# Trap_PCB_SMT2024_N_N.net
KiCad netlist of a schematic drawn in Altium Designer
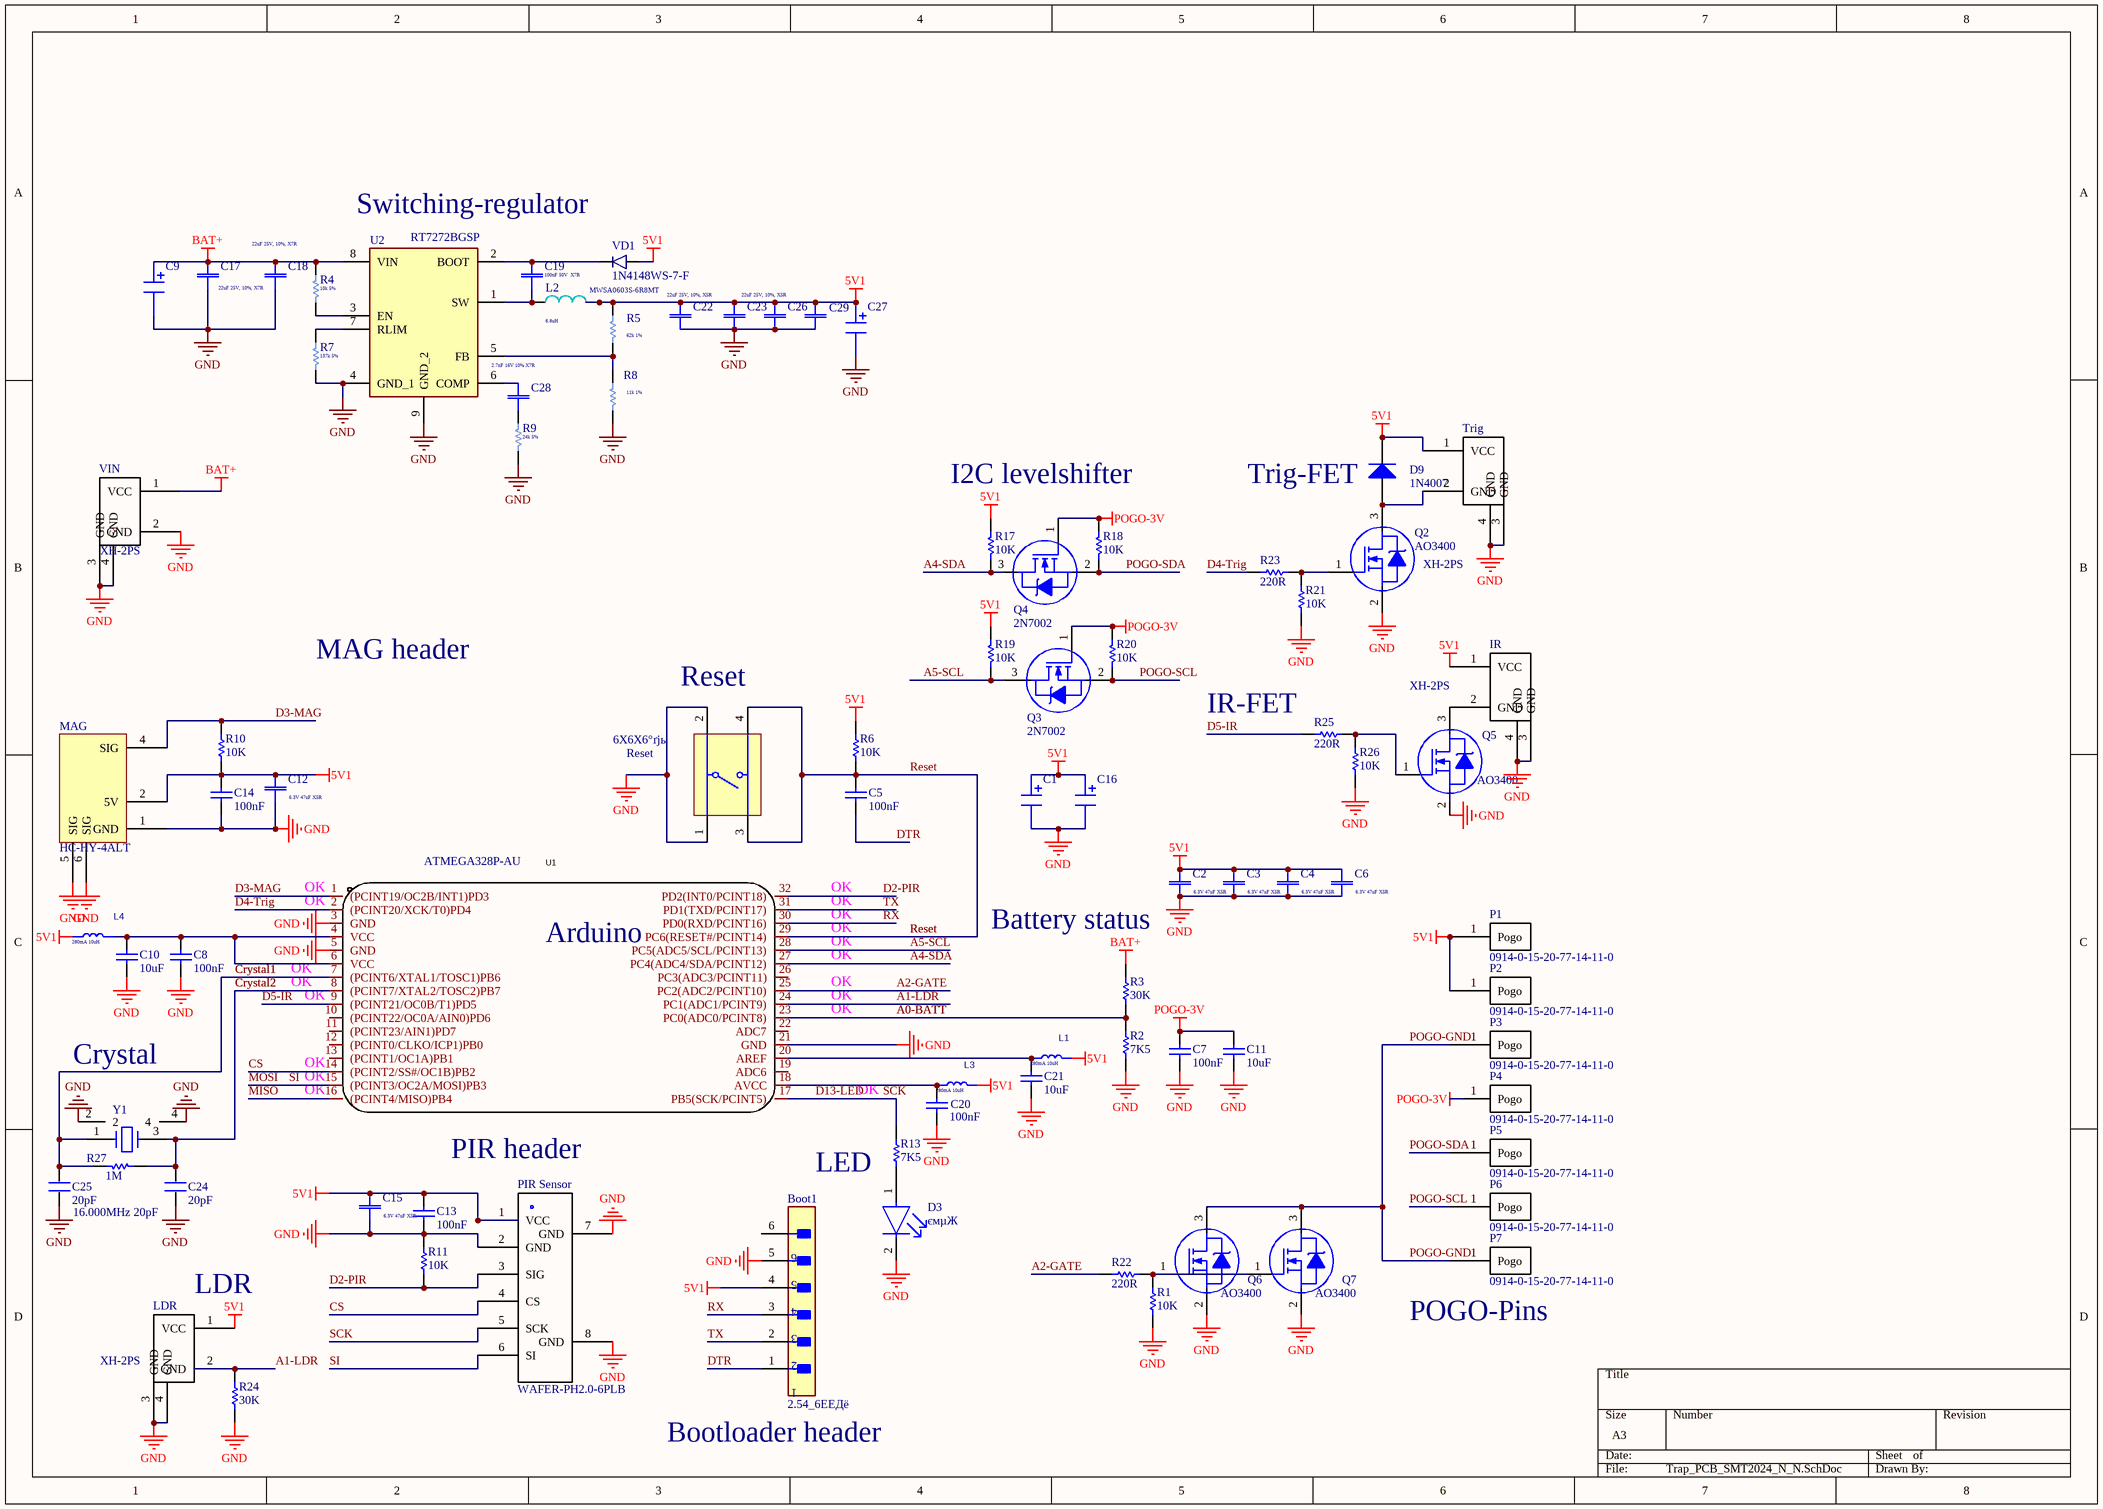
[diagram p0: Trap_PCB_SMT2024_N_N.SchDoc]

(export (version "E")
  (design (tool "Eeschema 10.0.6"))
  (components
    (comp (ref "Boot1")
      (value "2.54_6ЕЕДё")
      (footprint "FP-SWR25X-NRTC-S06-ST-BA-MFG")
      (description "CONN HEADER VERT 6POS 2.54MM")
      (fields
        (field (name "OCTOPART") "https://octopart.com/swr25x-nrtc-s06-st-ba-sullins-20912730")
        (field (name "MANUFACTURER") "Sullins")
      )
      (libsource (lib "*") (part "f2cb566baf1c37ab5a3b8e90bbeafd6"))
    )
    (comp (ref "C1")
      (value "NJCON 1026R30812R00")
      (footprint "Cap 8mm")
      (libsource (lib "MyLib1") (part "CAP 8mm"))
    )
    (comp (ref "C2")
      (value "6.3V 47uF X5R")
      (footprint "C0805(2013)")
      (description "SMD-0805")
      (libsource (lib "MyLib1") (part "C-0805"))
    )
    (comp (ref "C3")
      (value "6.3V 47uF X5R")
      (footprint "C0805(2013)")
      (description "SMD-0805")
      (libsource (lib "MyLib1") (part "C-0805"))
    )
    (comp (ref "C4")
      (value "6.3V 47uF X5R")
      (footprint "C0805(2013)")
      (description "SMD-0805")
      (libsource (lib "MyLib1") (part "C-0805"))
    )
    (comp (ref "C5")
      (value "100nF")
      (footprint "0603C")
      (description "Capacitor, Ceramic, 22 pF, +/-10 %, 100 V, -55 to 125 degC, 2-Pin THD, RoHS, Bulk")
      (libsource (lib "*") (part "CAP-NP-2"))
    )
    (comp (ref "C6")
      (value "6.3V 47uF X5R")
      (footprint "C0805(2013)")
      (description "SMD-0805")
      (libsource (lib "MyLib1") (part "C-0805"))
    )
    (comp (ref "C7")
      (value "100nF")
      (footprint "0603C")
      (description "Capacitor, Ceramic, 22 pF, +/-10 %, 100 V, -55 to 125 degC, 2-Pin THD, RoHS, Bulk")
      (libsource (lib "*") (part "CAP-NP-2"))
    )
    (comp (ref "C8")
      (value "100nF")
      (footprint "0603C")
      (description "Capacitor, Ceramic, 22 pF, +/-10 %, 100 V, -55 to 125 degC, 2-Pin THD, RoHS, Bulk")
      (libsource (lib "*") (part "CAP-NP-2"))
    )
    (comp (ref "C9")
      (value "Honor Elec HS1C567M0811PC")
      (footprint "Cap 8mm")
      (libsource (lib "MyLib1") (part "CAP 8mm"))
    )
    (comp (ref "C10")
      (value "10uF")
      (footprint "0603C")
      (description "Capacitor, Ceramic, 22 pF, +/-10 %, 100 V, -55 to 125 degC, 2-Pin THD, RoHS, Bulk")
      (libsource (lib "*") (part "CAP-NP-2"))
    )
    (comp (ref "C11")
      (value "10uF")
      (footprint "0603C")
      (description "Capacitor, Ceramic, 22 pF, +/-10 %, 100 V, -55 to 125 degC, 2-Pin THD, RoHS, Bulk")
      (libsource (lib "*") (part "CAP-NP-2"))
    )
    (comp (ref "C12")
      (value "6.3V 47uF X5R")
      (footprint "C0805(2013)")
      (description "SMD-0805")
      (libsource (lib "MyLib1") (part "C-0805"))
    )
    (comp (ref "C13")
      (value "100nF")
      (footprint "0603C")
      (description "Capacitor, Ceramic, 22 pF, +/-10 %, 100 V, -55 to 125 degC, 2-Pin THD, RoHS, Bulk")
      (libsource (lib "*") (part "CAP-NP-2"))
    )
    (comp (ref "C14")
      (value "100nF")
      (footprint "0603C")
      (description "Capacitor, Ceramic, 22 pF, +/-10 %, 100 V, -55 to 125 degC, 2-Pin THD, RoHS, Bulk")
      (libsource (lib "*") (part "CAP-NP-2"))
    )
    (comp (ref "C15")
      (value "6.3V 47uF X5R")
      (footprint "C0805(2013)")
      (description "SMD-0805")
      (libsource (lib "MyLib1") (part "C-0805"))
    )
    (comp (ref "C16")
      (value "NJCON 1026R30812R00")
      (footprint "Cap 8mm")
      (libsource (lib "MyLib1") (part "CAP 8mm"))
    )
    (comp (ref "C17")
      (value "22uF 25V, 10%, X7R")
      (footprint "C1206(3216)")
      (description "SMD-1206")
      (libsource (lib "MyLib1") (part "C-1206"))
    )
    (comp (ref "C18")
      (value "22uF 25V, 10%, X7R")
      (footprint "C1206(3216)")
      (description "SMD-1206")
      (libsource (lib "MyLib1") (part "C-1206"))
    )
    (comp (ref "C19")
      (value "100nF 50V  X7R")
      (footprint "C0603(1608)")
      (description "SMD-0603")
      (libsource (lib "MyLib1") (part "C-0603"))
    )
    (comp (ref "C20")
      (value "100nF")
      (footprint "0603C")
      (description "Capacitor, Ceramic, 22 pF, +/-10 %, 100 V, -55 to 125 degC, 2-Pin THD, RoHS, Bulk")
      (libsource (lib "*") (part "CAP-NP-2"))
    )
    (comp (ref "C21")
      (value "10uF")
      (footprint "0603C")
      (description "Capacitor, Ceramic, 22 pF, +/-10 %, 100 V, -55 to 125 degC, 2-Pin THD, RoHS, Bulk")
      (libsource (lib "*") (part "CAP-NP-2"))
    )
    (comp (ref "C22")
      (value "22uF 25V, 10%, X5R")
      (footprint "C0805(2013)")
      (description "SMD-0805")
      (libsource (lib "MyLib1") (part "C-0805"))
    )
    (comp (ref "C23")
      (value "22uF 25V, 10%, X5R")
      (footprint "C0805(2013)")
      (description "SMD-0805")
      (libsource (lib "MyLib1") (part "C-0805"))
    )
    (comp (ref "C24") (value "20pF") (footprint "0603C") (libsource (lib "*") (part "C")))
    (comp (ref "C25") (value "20pF") (footprint "0603C") (libsource (lib "*") (part "C")))
    (comp (ref "C26")
      (value "22uF 25V, 10%, X5R")
      (footprint "C0805(2013)")
      (description "SMD-0805")
      (libsource (lib "MyLib1") (part "C-0805"))
    )
    (comp (ref "C27")
      (value "NJCON 1026R30812R00")
      (footprint "Cap 8mm")
      (libsource (lib "MyLib1") (part "CAP 8mm"))
    )
    (comp (ref "C28")
      (value "2.7nF 16V 10% X7R")
      (footprint "C0603(1608)")
      (description "SMD-0603")
      (libsource (lib "MyLib1") (part "C-0603"))
    )
    (comp (ref "C29")
      (value "22uF 25V, 10%, X5R")
      (footprint "C0805(2013)")
      (description "SMD-0805")
      (libsource (lib "MyLib1") (part "C-0805"))
    )
    (comp (ref "D3")
      (value "ємµЖ")
      (footprint "0603LED")
      (description "LED YELLOW DIFFUSED T-1 T/H")
      (fields (field (name "MANUFACTURER") "Broadcom"))
      (libsource (lib "*") (part "8706943c75ba83719d021d2fdc84c58"))
    )
    (comp (ref "D9")
      (value "1N4007")
      (footprint "SMA")
      (description "Default Diode")
      (fields (field (name "PUBLISHER") "Altium Limited"))
      (libsource (lib "*") (part "Diode"))
    )
    (comp (ref "IR") (value "XH-2PS") (footprint "CNS_2.5-2") (libsource (lib "*") (part "JST HXP2")))
    (comp (ref "L1")
      (value "280mA 10uH")
      (footprint "R0603")
      (description "FTW1608FE100KT")
      (fields (field (name "Comment") "L-0603"))
      (libsource (lib "MyLib1") (part "L-0603"))
    )
    (comp (ref "L2")
      (value "MWSA0603S-6R8MT")
      (footprint "L (7.00mm x 6.60mm)")
      (description "6.8uH 5A 48mΩ SMD (7.00mm x 6.60mm)")
      (fields (field (name "ALTIUM_VALUE") "6.8uH"))
      (libsource (lib "MyLib1") (part "MWSA0603S-6R8MT"))
    )
    (comp (ref "L3")
      (value "280mA 10uH")
      (footprint "R0603")
      (description "FTW1608FE100KT")
      (fields (field (name "Comment") "L-0603"))
      (libsource (lib "MyLib1") (part "L-0603"))
    )
    (comp (ref "L4")
      (value "280mA 10uH")
      (footprint "R0603")
      (description "FTW1608FE100KT")
      (fields (field (name "Comment") "L-0603"))
      (libsource (lib "MyLib1") (part "L-0603"))
    )
    (comp (ref "LDR") (value "XH-2PS") (footprint "CNS_2.5-2") (libsource (lib "*") (part "JST HXP2")))
    (comp (ref "MAG")
      (value "HC-HY-4ALT")
      (footprint "CNS_4P-P2.0")
      (libsource (lib "*") (part "MAG Sensor"))
    )
    (comp (ref "P1")
      (value "0914-0-15-20-77-14-11-0")
      (footprint "0914-0-15-20-77-14-11-0")
      (description "CONTACT SPRING LOADED T/H GOLD")
      (libsource (lib "*") (part "0914-0-15-20-77-14-11-0"))
    )
    (comp (ref "P2")
      (value "0914-0-15-20-77-14-11-0")
      (footprint "0914-0-15-20-77-14-11-0")
      (description "CONTACT SPRING LOADED T/H GOLD")
      (libsource (lib "*") (part "0914-0-15-20-77-14-11-0"))
    )
    (comp (ref "P3")
      (value "0914-0-15-20-77-14-11-0")
      (footprint "0914-0-15-20-77-14-11-0")
      (description "CONTACT SPRING LOADED T/H GOLD")
      (libsource (lib "*") (part "0914-0-15-20-77-14-11-0"))
    )
    (comp (ref "P4")
      (value "0914-0-15-20-77-14-11-0")
      (footprint "0914-0-15-20-77-14-11-0")
      (description "CONTACT SPRING LOADED T/H GOLD")
      (libsource (lib "*") (part "0914-0-15-20-77-14-11-0"))
    )
    (comp (ref "P5")
      (value "0914-0-15-20-77-14-11-0")
      (footprint "0914-0-15-20-77-14-11-0")
      (description "CONTACT SPRING LOADED T/H GOLD")
      (libsource (lib "*") (part "0914-0-15-20-77-14-11-0"))
    )
    (comp (ref "P6")
      (value "0914-0-15-20-77-14-11-0")
      (footprint "0914-0-15-20-77-14-11-0")
      (description "CONTACT SPRING LOADED T/H GOLD")
      (libsource (lib "*") (part "0914-0-15-20-77-14-11-0"))
    )
    (comp (ref "P7")
      (value "0914-0-15-20-77-14-11-0")
      (footprint "0914-0-15-20-77-14-11-0")
      (description "CONTACT SPRING LOADED T/H GOLD")
      (libsource (lib "*") (part "0914-0-15-20-77-14-11-0"))
    )
    (comp (ref "PIR Sensor")
      (value "WAFER-PH2.0-6PLB")
      (footprint "CNS-2.0-6")
      (libsource (lib "*") (part "JST - PH-6p - 2.0mm"))
    )
    (comp (ref "Q2") (value "AO3400") (footprint "SOT-23") (libsource (lib "") (part "IRF640N_1")))
    (comp (ref "Q3") (value "2N7002") (footprint "SOT-23") (libsource (lib "Schlib1") (part "IRF640N")))
    (comp (ref "Q4") (value "2N7002") (footprint "SOT-23") (libsource (lib "Schlib1") (part "IRF640N")))
    (comp (ref "Q5") (value "AO3400") (footprint "SOT-23") (libsource (lib "") (part "IRF640N_1")))
    (comp (ref "Q6") (value "AO3400") (footprint "SOT-23") (libsource (lib "") (part "IRF640N_1")))
    (comp (ref "Q7") (value "AO3400") (footprint "SOT-23") (libsource (lib "") (part "IRF640N_1")))
    (comp (ref "R1")
      (value "10K")
      (footprint "0603R")
      (fields (field (name "TOLERANCE") "ЎА5%"))
      (libsource (lib "*") (part "RES-2"))
    )
    (comp (ref "R2")
      (value "7K5")
      (footprint "0603R")
      (fields (field (name "TOLERANCE") "ЎА5%"))
      (libsource (lib "*") (part "RES-2"))
    )
    (comp (ref "R3")
      (value "30K")
      (footprint "0603R")
      (fields (field (name "TOLERANCE") "ЎА5%"))
      (libsource (lib "*") (part "RES-2"))
    )
    (comp (ref "R4")
      (value "10k 5%")
      (footprint "R0603")
      (description "SMD 0603 0.1W 5% 50V")
      (libsource (lib "MyLib1") (part "R-0603"))
    )
    (comp (ref "R5")
      (value "62k 1%")
      (footprint "R0603")
      (description "SMD 0603 0.1W 5% 50V")
      (libsource (lib "MyLib1") (part "R-0603"))
    )
    (comp (ref "R6")
      (value "10K")
      (footprint "0603R")
      (fields (field (name "TOLERANCE") "ЎА5%"))
      (libsource (lib "*") (part "RES-2"))
    )
    (comp (ref "R7")
      (value "137k 5%")
      (footprint "R0603")
      (description "SMD 0603 0.1W 5% 50V")
      (libsource (lib "MyLib1") (part "R-0603"))
    )
    (comp (ref "R8")
      (value "11k 1%")
      (footprint "R0603")
      (description "SMD 0603 0.1W 5% 50V")
      (libsource (lib "MyLib1") (part "R-0603"))
    )
    (comp (ref "R9")
      (value "24k 5%")
      (footprint "R0603")
      (description "SMD 0603 0.1W 5% 50V")
      (libsource (lib "MyLib1") (part "R-0603"))
    )
    (comp (ref "R10")
      (value "10K")
      (footprint "0603R")
      (fields (field (name "TOLERANCE") "ЎА5%"))
      (libsource (lib "*") (part "RES-2"))
    )
    (comp (ref "R11")
      (value "10K")
      (footprint "0603R")
      (fields (field (name "TOLERANCE") "ЎА5%"))
      (libsource (lib "*") (part "RES-2"))
    )
    (comp (ref "R13")
      (value "7K5")
      (footprint "0603R")
      (fields (field (name "TOLERANCE") "ЎА5%"))
      (libsource (lib "*") (part "RES-2"))
    )
    (comp (ref "R17")
      (value "10K")
      (footprint "0603R")
      (fields (field (name "TOLERANCE") "ЎА5%"))
      (libsource (lib "*") (part "RES-2"))
    )
    (comp (ref "R18")
      (value "10K")
      (footprint "0603R")
      (fields (field (name "TOLERANCE") "ЎА5%"))
      (libsource (lib "*") (part "RES-2"))
    )
    (comp (ref "R19")
      (value "10K")
      (footprint "0603R")
      (fields (field (name "TOLERANCE") "ЎА5%"))
      (libsource (lib "*") (part "RES-2"))
    )
    (comp (ref "R20")
      (value "10K")
      (footprint "0603R")
      (fields (field (name "TOLERANCE") "ЎА5%"))
      (libsource (lib "*") (part "RES-2"))
    )
    (comp (ref "R21")
      (value "10K")
      (footprint "0603R")
      (fields (field (name "TOLERANCE") "ЎА5%"))
      (libsource (lib "*") (part "RES-2"))
    )
    (comp (ref "R22")
      (value "220R")
      (footprint "0603R")
      (fields (field (name "TOLERANCE") "ЎА5%"))
      (libsource (lib "*") (part "RES-2"))
    )
    (comp (ref "R23")
      (value "220R")
      (footprint "0603R")
      (fields (field (name "TOLERANCE") "ЎА5%"))
      (libsource (lib "*") (part "RES-2"))
    )
    (comp (ref "R24")
      (value "30K")
      (footprint "0603R")
      (fields (field (name "TOLERANCE") "ЎА5%"))
      (libsource (lib "*") (part "RES-2"))
    )
    (comp (ref "R25")
      (value "220R")
      (footprint "0603R")
      (fields (field (name "TOLERANCE") "ЎА5%"))
      (libsource (lib "*") (part "RES-2"))
    )
    (comp (ref "R26")
      (value "10K")
      (footprint "0603R")
      (fields (field (name "TOLERANCE") "ЎА5%"))
      (libsource (lib "*") (part "RES-2"))
    )
    (comp (ref "R27")
      (value "1M")
      (footprint "0603R")
      (description "Resistor")
      (fields (field (name "PUBLISHER") "Altium Limited"))
      (libsource (lib "Miscellaneous Devices") (part "Res1"))
    )
    (comp (ref "Reset")
      (value "6X6X6°ґјь")
      (footprint "SW-4P-6X6")
      (description "Tactile Switch, SPST-NO, 0.05 A, 5 to 24 V, -25 to 70 degC, 4-Pin THD, RoHS, Bulk")
      (libsource (lib "*") (part "SW-SPST-4_A"))
    )
    (comp (ref "Trig") (value "XH-2PS") (footprint "CNS_2.5-2") (libsource (lib "*") (part "JST HXP2")))
    (comp (ref "U1")
      (value "ATMEGA328P-AU")
      (footprint "TQFP-32_L7.0-W7.0-P0.80-LS9.0-BL")
      (libsource (lib "altium-import") (part "root_0_ATMEGA328P-AU_"))
    )
    (comp (ref "U2")
      (value "RT7272BGSP")
      (footprint "SOIC8 +")
      (fields (field (name "MF") "Richtek USA"))
      (libsource (lib "MYLIB1") (part "RT7272BGSP"))
    )
    (comp (ref "VD1")
      (value "1N4148WS-7-F")
      (footprint "SOD-323")
      (libsource (lib "MYLIB1") (part "1N4148WS-7-F"))
    )
    (comp (ref "VIN") (value "XH-2PS") (footprint "CNS_2.5-2") (libsource (lib "*") (part "JST HXP2")))
    (comp (ref "Y1")
      (value "16.000MHz 20pF")
      (footprint "X3225")
      (description "R25010031/№¤ТµC/Пы·СA/ѕ§МеХсµґЖч/8.000M/20pF/ЎА30ppm/49USM/ROHS/-10Ўж~+70Ўж")
      (libsource (lib "R25_IC") (part "R25010031"))
    )
  )
  (nets
    (net (code "1") (name "/A0-BATT") (class "Default")
      (node (ref "R2") (pin "1") (pinfunction "1_1") (pintype "passive"))
      (node (ref "R3") (pin "2") (pinfunction "2_2") (pintype "passive"))
      (node (ref "U1") (pin "23") (pinfunction "PC0(ADC0/PCINT8)_23") (pintype "passive"))
    )
    (net (code "2") (name "/A1-LDR") (class "Default")
      (node (ref "LDR") (pin "2") (pinfunction "GND_2") (pintype "passive"))
      (node (ref "R24") (pin "2") (pinfunction "2_2") (pintype "passive"))
      (node (ref "U1") (pin "24") (pinfunction "PC1(ADC1/PCINT9)_24") (pintype "passive"))
    )
    (net (code "3") (name "/A2-GATE") (class "Default")
      (node (ref "R22") (pin "2") (pinfunction "2_2") (pintype "passive"))
      (node (ref "U1") (pin "25") (pinfunction "PC2(ADC2/PCINT10)_25") (pintype "passive"))
    )
    (net (code "4") (name "/A4-SDA") (class "Default")
      (node (ref "Q4") (pin "3") (pinfunction "3_3") (pintype "passive"))
      (node (ref "R17") (pin "1") (pinfunction "1_1") (pintype "passive"))
      (node (ref "U1") (pin "27") (pinfunction "PC4(ADC4/SDA/PCINT12)_27") (pintype "passive"))
    )
    (net (code "5") (name "/A5-SCL") (class "Default")
      (node (ref "Q3") (pin "3") (pinfunction "3_3") (pintype "passive"))
      (node (ref "R19") (pin "1") (pinfunction "1_1") (pintype "passive"))
      (node (ref "U1") (pin "28") (pinfunction "PC5(ADC5/SCL/PCINT13)_28") (pintype "passive"))
    )
    (net (code "6") (name "/CS") (class "Default")
      (node (ref "PIR Sensor") (pin "4") (pinfunction "CS_4") (pintype "passive"))
      (node (ref "U1") (pin "14") (pinfunction "(PCINT2/SS#/OC1B)PB2_14") (pintype "passive"))
    )
    (net (code "7") (name "/Crystal1") (class "Default")
      (node (ref "C25") (pin "2") (pintype "passive"))
      (node (ref "R27") (pin "2") (pinfunction "2_2") (pintype "passive"))
      (node (ref "U1") (pin "7") (pinfunction "(PCINT6/XTAL1/TOSC1)PB6_7") (pintype "passive"))
      (node (ref "Y1") (pin "1") (pinfunction "1_1") (pintype "passive"))
    )
    (net (code "8") (name "/Crystal2") (class "Default")
      (node (ref "C24") (pin "2") (pintype "passive"))
      (node (ref "R27") (pin "1") (pinfunction "1_1") (pintype "passive"))
      (node (ref "U1") (pin "8") (pinfunction "(PCINT7/XTAL2/TOSC2)PB7_8") (pintype "passive"))
      (node (ref "Y1") (pin "3") (pinfunction "3_3") (pintype "passive"))
    )
    (net (code "9") (name "/D2-PIR") (class "Default")
      (node (ref "PIR Sensor") (pin "3") (pinfunction "SIG_3") (pintype "passive"))
      (node (ref "R11") (pin "2") (pinfunction "2_2") (pintype "passive"))
      (node (ref "U1") (pin "32") (pinfunction "PD2(INT0/PCINT18)_32") (pintype "passive"))
    )
    (net (code "10") (name "/D3-MAG") (class "Default")
      (node (ref "MAG") (pin "4") (pinfunction "SIG_4") (pintype "passive"))
      (node (ref "R10") (pin "1") (pinfunction "1_1") (pintype "passive"))
      (node (ref "U1") (pin "1") (pinfunction "(PCINT19/OC2B/INT1)PD3_1") (pintype "passive"))
    )
    (net (code "11") (name "/D4-Trig") (class "Default")
      (node (ref "R23") (pin "2") (pinfunction "2_2") (pintype "passive"))
      (node (ref "U1") (pin "2") (pinfunction "(PCINT20/XCK/T0)PD4_2") (pintype "passive"))
    )
    (net (code "12") (name "/D5-IR") (class "Default")
      (node (ref "R25") (pin "2") (pinfunction "2_2") (pintype "passive"))
      (node (ref "U1") (pin "9") (pinfunction "(PCINT21/OC0B/T1)PD5_9") (pintype "passive"))
    )
    (net (code "13") (name "/D13-LED") (class "Default")
      (node (ref "PIR Sensor") (pin "5") (pinfunction "SCK_5") (pintype "passive"))
      (node (ref "R13") (pin "2") (pinfunction "2_2") (pintype "passive"))
      (node (ref "U1") (pin "17") (pinfunction "PB5(SCK/PCINT5)_17") (pintype "passive"))
    )
    (net (code "14") (name "/DTR") (class "Default")
      (node (ref "Boot1") (pin "1") (pinfunction "1_1") (pintype "passive"))
      (node (ref "C5") (pin "1") (pinfunction "1_1") (pintype "passive"))
    )
    (net (code "15") (name "/MISO") (class "Default")
      (node (ref "U1") (pin "16") (pinfunction "(PCINT4/MISO)PB4_16") (pintype "passive"))
    )
    (net (code "16") (name "/MOSI") (class "Default")
      (node (ref "PIR Sensor") (pin "6") (pinfunction "SI_6") (pintype "passive"))
      (node (ref "U1") (pin "15") (pinfunction "(PCINT3/OC2A/MOSI)PB3_15") (pintype "passive"))
    )
    (net (code "17") (name "/POGO-GND") (class "Default")
      (node (ref "P3") (pin "1") (pinfunction "Pogo_1") (pintype "passive"))
      (node (ref "P7") (pin "1") (pinfunction "Pogo_1") (pintype "passive"))
      (node (ref "Q6") (pin "3") (pinfunction "3_3") (pintype "passive"))
      (node (ref "Q7") (pin "3") (pinfunction "3_3") (pintype "passive"))
    )
    (net (code "18") (name "/POGO-SCL") (class "Default")
      (node (ref "P6") (pin "1") (pinfunction "Pogo_1") (pintype "passive"))
      (node (ref "Q3") (pin "2") (pinfunction "2_2") (pintype "passive"))
      (node (ref "R20") (pin "1") (pinfunction "1_1") (pintype "passive"))
    )
    (net (code "19") (name "/POGO-SDA") (class "Default")
      (node (ref "P5") (pin "1") (pinfunction "Pogo_1") (pintype "passive"))
      (node (ref "Q4") (pin "2") (pinfunction "2_2") (pintype "passive"))
      (node (ref "R18") (pin "1") (pinfunction "1_1") (pintype "passive"))
    )
    (net (code "20") (name "/RX") (class "Default")
      (node (ref "Boot1") (pin "3") (pinfunction "3_3") (pintype "passive"))
      (node (ref "U1") (pin "30") (pinfunction "PD0(RXD/PCINT16)_30") (pintype "passive"))
    )
    (net (code "21") (name "/Reset") (class "Default")
      (node (ref "C5") (pin "2") (pinfunction "2_2") (pintype "passive"))
      (node (ref "R6") (pin "2") (pinfunction "2_2") (pintype "passive"))
      (node (ref "Reset") (pin "3") (pinfunction "3_3") (pintype "passive"))
      (node (ref "Reset") (pin "4") (pinfunction "4_4") (pintype "passive"))
      (node (ref "U1") (pin "29") (pinfunction "PC6(RESET#/PCINT14)_29") (pintype "passive"))
    )
    (net (code "22") (name "/TX") (class "Default")
      (node (ref "Boot1") (pin "2") (pinfunction "2_2") (pintype "passive"))
      (node (ref "U1") (pin "31") (pinfunction "PD1(TXD/PCINT17)_31") (pintype "passive"))
    )
    (net (code "23") (name "5V1") (class "Default")
      (node (ref "Boot1") (pin "4") (pinfunction "4_4") (pintype "passive"))
      (node (ref "C1") (pin "1") (pintype "passive"))
      (node (ref "C12") (pin "2") (pinfunction "2_2") (pintype "passive"))
      (node (ref "C13") (pin "2") (pinfunction "2_2") (pintype "passive"))
      (node (ref "C14") (pin "2") (pinfunction "2_2") (pintype "passive"))
      (node (ref "C15") (pin "2") (pinfunction "2_2") (pintype "passive"))
      (node (ref "C16") (pin "1") (pintype "passive"))
      (node (ref "C2") (pin "2") (pinfunction "2_2") (pintype "passive"))
      (node (ref "C22") (pin "2") (pinfunction "2_2") (pintype "passive"))
      (node (ref "C23") (pin "2") (pinfunction "2_2") (pintype "passive"))
      (node (ref "C26") (pin "2") (pinfunction "2_2") (pintype "passive"))
      (node (ref "C27") (pin "1") (pintype "passive"))
      (node (ref "C29") (pin "2") (pinfunction "2_2") (pintype "passive"))
      (node (ref "C3") (pin "2") (pinfunction "2_2") (pintype "passive"))
      (node (ref "C4") (pin "2") (pinfunction "2_2") (pintype "passive"))
      (node (ref "C6") (pin "2") (pinfunction "2_2") (pintype "passive"))
      (node (ref "D9") (pin "2") (pinfunction "K_2") (pintype "passive"))
      (node (ref "IR") (pin "1") (pinfunction "VCC_1") (pintype "passive"))
      (node (ref "L1") (pin "2") (pinfunction "2_2") (pintype "passive"))
      (node (ref "L2") (pin "2") (pintype "passive"))
      (node (ref "L3") (pin "2") (pinfunction "2_2") (pintype "passive"))
      (node (ref "L4") (pin "1") (pinfunction "1_1") (pintype "passive"))
      (node (ref "LDR") (pin "1") (pinfunction "VCC_1") (pintype "passive"))
      (node (ref "MAG") (pin "2") (pinfunction "5V_2") (pintype "passive"))
      (node (ref "P1") (pin "1") (pinfunction "Pogo_1") (pintype "passive"))
      (node (ref "P2") (pin "1") (pinfunction "Pogo_1") (pintype "passive"))
      (node (ref "PIR Sensor") (pin "1") (pinfunction "VCC_1") (pintype "passive"))
      (node (ref "R10") (pin "2") (pinfunction "2_2") (pintype "passive"))
      (node (ref "R17") (pin "2") (pinfunction "2_2") (pintype "passive"))
      (node (ref "R19") (pin "2") (pinfunction "2_2") (pintype "passive"))
      (node (ref "R5") (pin "1") (pinfunction "1_1") (pintype "passive"))
      (node (ref "R6") (pin "1") (pinfunction "1_1") (pintype "passive"))
      (node (ref "Trig") (pin "1") (pinfunction "VCC_1") (pintype "passive"))
      (node (ref "VD1") (pin "2") (pinfunction "A_2") (pintype "passive"))
    )
    (net (code "24") (name "BAT+") (class "Default")
      (node (ref "C17") (pin "2") (pinfunction "2_2") (pintype "passive"))
      (node (ref "C18") (pin "2") (pinfunction "2_2") (pintype "passive"))
      (node (ref "C9") (pin "1") (pintype "passive"))
      (node (ref "R3") (pin "1") (pinfunction "1_1") (pintype "passive"))
      (node (ref "R4") (pin "1") (pinfunction "1_1") (pintype "passive"))
      (node (ref "U2") (pin "8") (pinfunction "VIN_8") (pintype "passive"))
      (node (ref "VIN") (pin "1") (pinfunction "VCC_1") (pintype "passive"))
    )
    (net (code "25") (name "GND") (class "Default")
      (node (ref "Boot1") (pin "5") (pinfunction "5_5") (pintype "passive"))
      (node (ref "C1") (pin "2") (pintype "passive"))
      (node (ref "C10") (pin "1") (pinfunction "1_1") (pintype "passive"))
      (node (ref "C11") (pin "1") (pinfunction "1_1") (pintype "passive"))
      (node (ref "C12") (pin "1") (pinfunction "1_1") (pintype "passive"))
      (node (ref "C13") (pin "1") (pinfunction "1_1") (pintype "passive"))
      (node (ref "C14") (pin "1") (pinfunction "1_1") (pintype "passive"))
      (node (ref "C15") (pin "1") (pinfunction "1_1") (pintype "passive"))
      (node (ref "C16") (pin "2") (pintype "passive"))
      (node (ref "C17") (pin "1") (pinfunction "1_1") (pintype "passive"))
      (node (ref "C18") (pin "1") (pinfunction "1_1") (pintype "passive"))
      (node (ref "C2") (pin "1") (pinfunction "1_1") (pintype "passive"))
      (node (ref "C20") (pin "1") (pinfunction "1_1") (pintype "passive"))
      (node (ref "C21") (pin "1") (pinfunction "1_1") (pintype "passive"))
      (node (ref "C22") (pin "1") (pinfunction "1_1") (pintype "passive"))
      (node (ref "C23") (pin "1") (pinfunction "1_1") (pintype "passive"))
      (node (ref "C24") (pin "1") (pintype "passive"))
      (node (ref "C25") (pin "1") (pintype "passive"))
      (node (ref "C26") (pin "1") (pinfunction "1_1") (pintype "passive"))
      (node (ref "C27") (pin "2") (pintype "passive"))
      (node (ref "C29") (pin "1") (pinfunction "1_1") (pintype "passive"))
      (node (ref "C3") (pin "1") (pinfunction "1_1") (pintype "passive"))
      (node (ref "C4") (pin "1") (pinfunction "1_1") (pintype "passive"))
      (node (ref "C6") (pin "1") (pinfunction "1_1") (pintype "passive"))
      (node (ref "C7") (pin "1") (pinfunction "1_1") (pintype "passive"))
      (node (ref "C8") (pin "1") (pinfunction "1_1") (pintype "passive"))
      (node (ref "C9") (pin "2") (pintype "passive"))
      (node (ref "D3") (pin "2") (pinfunction "A_2") (pintype "passive"))
      (node (ref "IR") (pin "3") (pinfunction "GND_3") (pintype "passive"))
      (node (ref "IR") (pin "4") (pinfunction "GND_4") (pintype "passive"))
      (node (ref "LDR") (pin "3") (pinfunction "GND_3") (pintype "passive"))
      (node (ref "LDR") (pin "4") (pinfunction "GND_4") (pintype "passive"))
      (node (ref "MAG") (pin "1") (pinfunction "GND_1") (pintype "passive"))
      (node (ref "MAG") (pin "5") (pinfunction "SIG_5") (pintype "passive"))
      (node (ref "MAG") (pin "6") (pinfunction "SIG_6") (pintype "passive"))
      (node (ref "PIR Sensor") (pin "2") (pinfunction "GND_2") (pintype "passive"))
      (node (ref "PIR Sensor") (pin "7") (pinfunction "GND_7") (pintype "passive"))
      (node (ref "PIR Sensor") (pin "8") (pinfunction "GND_8") (pintype "passive"))
      (node (ref "Q2") (pin "2") (pinfunction "2_2") (pintype "passive"))
      (node (ref "Q5") (pin "2") (pinfunction "2_2") (pintype "passive"))
      (node (ref "Q6") (pin "2") (pinfunction "2_2") (pintype "passive"))
      (node (ref "Q7") (pin "2") (pinfunction "2_2") (pintype "passive"))
      (node (ref "R1") (pin "1") (pinfunction "1_1") (pintype "passive"))
      (node (ref "R11") (pin "1") (pinfunction "1_1") (pintype "passive"))
      (node (ref "R2") (pin "2") (pinfunction "2_2") (pintype "passive"))
      (node (ref "R21") (pin "1") (pinfunction "1_1") (pintype "passive"))
      (node (ref "R24") (pin "1") (pinfunction "1_1") (pintype "passive"))
      (node (ref "R26") (pin "1") (pinfunction "1_1") (pintype "passive"))
      (node (ref "R7") (pin "2") (pinfunction "2_2") (pintype "passive"))
      (node (ref "R8") (pin "2") (pinfunction "2_2") (pintype "passive"))
      (node (ref "R9") (pin "2") (pinfunction "2_2") (pintype "passive"))
      (node (ref "Reset") (pin "1") (pinfunction "1_1") (pintype "passive"))
      (node (ref "Reset") (pin "2") (pinfunction "2_2") (pintype "passive"))
      (node (ref "Trig") (pin "3") (pinfunction "GND_3") (pintype "passive"))
      (node (ref "Trig") (pin "4") (pinfunction "GND_4") (pintype "passive"))
      (node (ref "U1") (pin "21") (pinfunction "GND_21") (pintype "passive"))
      (node (ref "U1") (pin "3") (pinfunction "GND_3") (pintype "passive"))
      (node (ref "U1") (pin "5") (pinfunction "GND_5") (pintype "passive"))
      (node (ref "U2") (pin "4") (pinfunction "GND_1_4") (pintype "passive"))
      (node (ref "U2") (pin "9") (pinfunction "GND_2_9") (pintype "passive"))
      (node (ref "VIN") (pin "2") (pinfunction "GND_2") (pintype "passive"))
      (node (ref "VIN") (pin "3") (pinfunction "GND_3") (pintype "passive"))
      (node (ref "VIN") (pin "4") (pinfunction "GND_4") (pintype "passive"))
      (node (ref "Y1") (pin "2") (pinfunction "2_2") (pintype "passive"))
      (node (ref "Y1") (pin "4") (pinfunction "4_4") (pintype "passive"))
    )
    (net (code "26") (name "Net-(C10-Pad2)") (class "Default")
      (node (ref "C10") (pin "2") (pinfunction "2_2") (pintype "passive"))
      (node (ref "C8") (pin "2") (pinfunction "2_2") (pintype "passive"))
      (node (ref "L4") (pin "2") (pinfunction "2_2") (pintype "passive"))
      (node (ref "U1") (pin "4") (pinfunction "VCC_4") (pintype "passive"))
      (node (ref "U1") (pin "6") (pinfunction "VCC_6") (pintype "passive"))
    )
    (net (code "27") (name "Net-(C28-Pad1)") (class "Default")
      (node (ref "C28") (pin "1") (pinfunction "1_1") (pintype "passive"))
      (node (ref "R9") (pin "1") (pinfunction "1_1") (pintype "passive"))
    )
    (net (code "28") (name "Net-(D3-C)") (class "Default")
      (node (ref "D3") (pin "1") (pinfunction "C_1") (pintype "passive"))
      (node (ref "R13") (pin "1") (pinfunction "1_1") (pintype "passive"))
    )
    (net (code "29") (name "Net-(D9-A)") (class "Default")
      (node (ref "D9") (pin "1") (pinfunction "A_1") (pintype "passive"))
      (node (ref "Q2") (pin "3") (pinfunction "3_3") (pintype "passive"))
      (node (ref "Trig") (pin "2") (pinfunction "GND_2") (pintype "passive"))
    )
    (net (code "30") (name "Net-(IR-GND-Pad2)") (class "Default")
      (node (ref "IR") (pin "2") (pinfunction "GND_2") (pintype "passive"))
      (node (ref "Q5") (pin "3") (pinfunction "3_3") (pintype "passive"))
    )
    (net (code "31") (name "Net-(Q2-Pad1)") (class "Default")
      (node (ref "Q2") (pin "1") (pinfunction "1_1") (pintype "passive"))
      (node (ref "R21") (pin "2") (pinfunction "2_2") (pintype "passive"))
      (node (ref "R23") (pin "1") (pinfunction "1_1") (pintype "passive"))
    )
    (net (code "32") (name "Net-(Q5-Pad1)") (class "Default")
      (node (ref "Q5") (pin "1") (pinfunction "1_1") (pintype "passive"))
      (node (ref "R25") (pin "1") (pinfunction "1_1") (pintype "passive"))
      (node (ref "R26") (pin "2") (pinfunction "2_2") (pintype "passive"))
    )
    (net (code "33") (name "Net-(Q6-Pad1)") (class "Default")
      (node (ref "Q6") (pin "1") (pinfunction "1_1") (pintype "passive"))
      (node (ref "Q7") (pin "1") (pinfunction "1_1") (pintype "passive"))
      (node (ref "R1") (pin "2") (pinfunction "2_2") (pintype "passive"))
      (node (ref "R22") (pin "1") (pinfunction "1_1") (pintype "passive"))
    )
    (net (code "34") (name "Net-(U1-AREF)") (class "Default")
      (node (ref "C21") (pin "2") (pinfunction "2_2") (pintype "passive"))
      (node (ref "L1") (pin "1") (pinfunction "1_1") (pintype "passive"))
      (node (ref "U1") (pin "20") (pinfunction "AREF_20") (pintype "passive"))
    )
    (net (code "35") (name "Net-(U1-AVCC)") (class "Default")
      (node (ref "C20") (pin "2") (pinfunction "2_2") (pintype "passive"))
      (node (ref "L3") (pin "1") (pinfunction "1_1") (pintype "passive"))
      (node (ref "U1") (pin "18") (pinfunction "AVCC_18") (pintype "passive"))
    )
    (net (code "36") (name "Net-(U2-BOOT)") (class "Default")
      (node (ref "C19") (pin "2") (pinfunction "2_2") (pintype "passive"))
      (node (ref "U2") (pin "2") (pinfunction "BOOT_2") (pintype "passive"))
      (node (ref "VD1") (pin "1") (pinfunction "K_1") (pintype "passive"))
    )
    (net (code "37") (name "Net-(U2-COMP)") (class "Default")
      (node (ref "C28") (pin "2") (pinfunction "2_2") (pintype "passive"))
      (node (ref "U2") (pin "6") (pinfunction "COMP_6") (pintype "passive"))
    )
    (net (code "38") (name "Net-(U2-EN)") (class "Default")
      (node (ref "R4") (pin "2") (pinfunction "2_2") (pintype "passive"))
      (node (ref "U2") (pin "3") (pinfunction "EN_3") (pintype "passive"))
    )
    (net (code "39") (name "Net-(U2-FB)") (class "Default")
      (node (ref "R5") (pin "2") (pinfunction "2_2") (pintype "passive"))
      (node (ref "R8") (pin "1") (pinfunction "1_1") (pintype "passive"))
      (node (ref "U2") (pin "5") (pinfunction "FB_5") (pintype "passive"))
    )
    (net (code "40") (name "Net-(U2-RLIM)") (class "Default")
      (node (ref "R7") (pin "1") (pinfunction "1_1") (pintype "passive"))
      (node (ref "U2") (pin "7") (pinfunction "RLIM_7") (pintype "passive"))
    )
    (net (code "41") (name "Net-(U2-SW)") (class "Default")
      (node (ref "C19") (pin "1") (pinfunction "1_1") (pintype "passive"))
      (node (ref "L2") (pin "1") (pintype "passive"))
      (node (ref "U2") (pin "1") (pinfunction "SW_1") (pintype "passive"))
    )
    (net (code "42") (name "POGO-3V") (class "Default")
      (node (ref "C11") (pin "2") (pinfunction "2_2") (pintype "passive"))
      (node (ref "C7") (pin "2") (pinfunction "2_2") (pintype "passive"))
      (node (ref "P4") (pin "1") (pinfunction "Pogo_1") (pintype "passive"))
      (node (ref "Q3") (pin "1") (pinfunction "1_1") (pintype "passive"))
      (node (ref "Q4") (pin "1") (pinfunction "1_1") (pintype "passive"))
      (node (ref "R18") (pin "2") (pinfunction "2_2") (pintype "passive"))
      (node (ref "R20") (pin "2") (pinfunction "2_2") (pintype "passive"))
    )
    (net (code "43") (name "unconnected-(Boot1-Pad6)") (class "Default")
      (node (ref "Boot1") (pin "6") (pinfunction "6_6") (pintype "passive"))
    )
    (net (code "44") (name "unconnected-(U1-(PCINT0{slash}CLKO{slash}ICP1)PB0-Pad12)") (class "Default")
      (node (ref "U1") (pin "12") (pinfunction "(PCINT0/CLKO/ICP1)PB0_12") (pintype "passive"))
    )
    (net (code "45") (name "unconnected-(U1-(PCINT1{slash}OC1A)PB1-Pad13)") (class "Default")
      (node (ref "U1") (pin "13") (pinfunction "(PCINT1/OC1A)PB1_13") (pintype "passive"))
    )
    (net (code "46") (name "unconnected-(U1-(PCINT22{slash}OC0A{slash}AIN0)PD6-Pad10)") (class "Default")
      (node (ref "U1") (pin "10") (pinfunction "(PCINT22/OC0A/AIN0)PD6_10") (pintype "passive"))
    )
    (net (code "47") (name "unconnected-(U1-(PCINT23{slash}AIN1)PD7-Pad11)") (class "Default")
      (node (ref "U1") (pin "11") (pinfunction "(PCINT23/AIN1)PD7_11") (pintype "passive"))
    )
    (net (code "48") (name "unconnected-(U1-ADC6-Pad19)") (class "Default")
      (node (ref "U1") (pin "19") (pinfunction "ADC6_19") (pintype "passive"))
    )
    (net (code "49") (name "unconnected-(U1-ADC7-Pad22)") (class "Default")
      (node (ref "U1") (pin "22") (pinfunction "ADC7_22") (pintype "passive"))
    )
    (net (code "50") (name "unconnected-(U1-PC3(ADC3{slash}PCINT11)-Pad26)") (class "Default")
      (node (ref "U1") (pin "26") (pinfunction "PC3(ADC3/PCINT11)_26") (pintype "passive"))
    )
  )
)
